# Photoresistors.net
KiCad netlist of a schematic drawn in Altium Designer
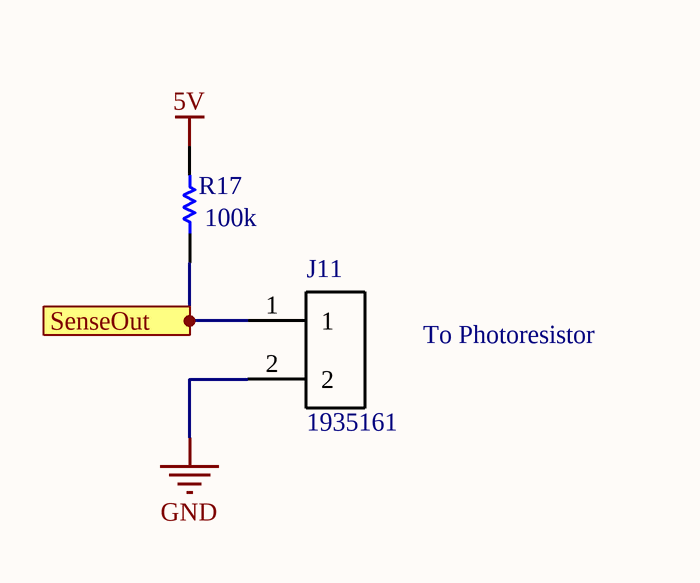
[diagram p0: Photoresistors.SchDoc]

(export (version "E")
  (design (tool "Eeschema 10.0.6"))
  (components
    (comp (ref "J11")
      (value "1935161")
      (footprint "PHOENIX_1935161")
      (description "Conn Terminal Blocks 2 POS 5mm Solder ST Thru-Hole 16A")
      (fields (field (name "DIGI-KEY_PART_NUMBER") "277-1667-ND") (field (name "MF") "Phoenix Contact"))
      (libsource (lib "Laser") (part "1935161"))
    )
    (comp (ref "R17")
      (value "100k")
      (footprint "AXIAL-0.3")
      (description "Resistor")
      (fields (field (name "Comment") "Res1") (field (name "PUBLISHER") "Altium Limited"))
      (libsource (lib "Miscellaneous Devices") (part "Res1"))
    )
  )
  (nets
    (net (code "1") (name "/SenseOut") (class "Default")
      (node (ref "J11") (pin "1") (pinfunction "1_1") (pintype "passive"))
      (node (ref "R17") (pin "1") (pinfunction "1_1") (pintype "passive"))
    )
    (net (code "2") (name "5V") (class "Default")
      (node (ref "R17") (pin "2") (pinfunction "2_2") (pintype "passive"))
    )
    (net (code "3") (name "GND") (class "Default")
      (node (ref "J11") (pin "2") (pinfunction "2_2") (pintype "passive"))
    )
  )
)
